# mp3431-boost-tester-mk-2_0_0.net
KiCad netlist of a schematic drawn in EAGLE
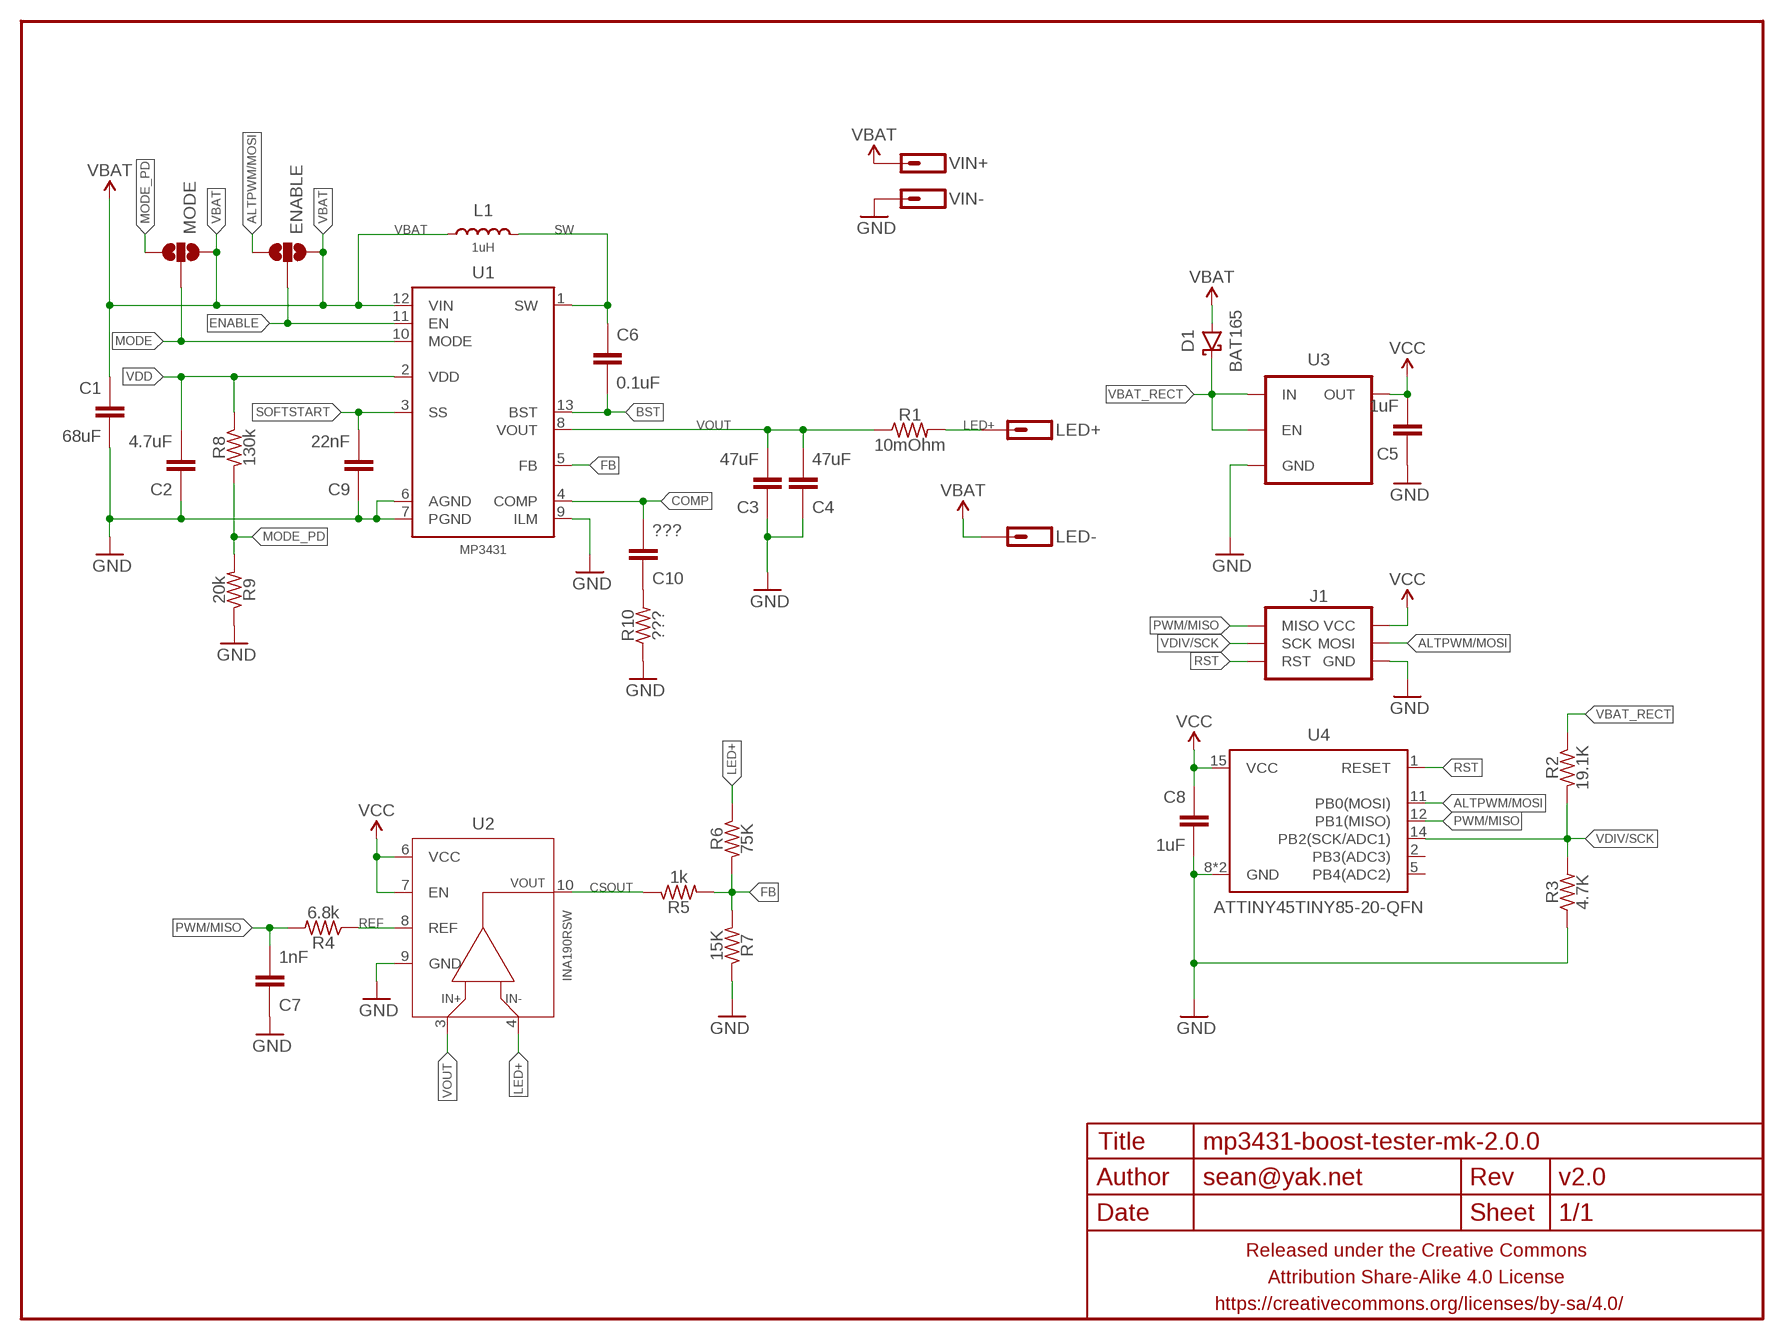
[diagram p0: schematic, sheet 1]

(export (version "E")
  (design (tool "Eeschema 10.0.6"))
  (components
    (comp (ref "C1")
      (value "68uF")
      (footprint "eagle-import:C1206")
      (libsource (lib "eagle-import") (part "CAPACITOR-CERAMICC1206"))
    )
    (comp (ref "C2")
      (value "4.7uF")
      (footprint "eagle-import:C0402")
      (libsource (lib "eagle-import") (part "CAPACITOR-CERAMICC0402"))
    )
    (comp (ref "C3")
      (value "47uF")
      (footprint "eagle-import:C1206")
      (libsource (lib "eagle-import") (part "CAPACITOR-CERAMICC1206"))
    )
    (comp (ref "C4")
      (value "47uF")
      (footprint "eagle-import:C1206")
      (libsource (lib "eagle-import") (part "CAPACITOR-CERAMICC1206"))
    )
    (comp (ref "C5")
      (value "1uF")
      (footprint "eagle-import:C0402")
      (libsource (lib "eagle-import") (part "CAPACITOR-CERAMICC0402"))
    )
    (comp (ref "C6")
      (value "0.1uF")
      (footprint "eagle-import:C0402")
      (libsource (lib "eagle-import") (part "CAPACITOR-CERAMICC0402"))
    )
    (comp (ref "C7")
      (value "1nF")
      (footprint "eagle-import:C0402")
      (libsource (lib "eagle-import") (part "CAPACITOR-CERAMICC0402"))
    )
    (comp (ref "C8")
      (value "1uF")
      (footprint "eagle-import:C0402")
      (libsource (lib "eagle-import") (part "CAPACITOR-CERAMICC0402"))
    )
    (comp (ref "C9")
      (value "22nF")
      (footprint "eagle-import:C0402")
      (libsource (lib "eagle-import") (part "CAPACITOR-CERAMICC0402"))
    )
    (comp (ref "C10")
      (value "???")
      (footprint "eagle-import:C0402")
      (libsource (lib "eagle-import") (part "CAPACITOR-CERAMICC0402"))
    )
    (comp (ref "D1")
      (value "BAT165")
      (footprint "eagle-import:SOD323-SCHOTTKY")
      (libsource (lib "eagle-import") (part "DIODE-SCHOTTKYSOD323"))
    )
    (comp (ref "ENABLE")
      (value "JUMPER-PAD-3-NOSMALL_BOX_SILK")
      (footprint "eagle-import:PAD-JUMPER-3-NO_YES_SILK_SMALL_BOX")
      (libsource (lib "eagle-import") (part "JUMPER-PAD-3-NOSMALL_BOX_SILK"))
    )
    (comp (ref "FRAME1")
      (value "FRAME-LETTERNO_PACKAGE")
      (footprint "eagle-import:DUMMY")
      (fields
        (field (name "DESIGNER") "sean@yak.net")
        (field (name "VERSION") "v2.0")
        (field (name "DESIGNER_1") "sean@yak.net")
        (field (name "VERSION_1") "v2.0")
      )
      (libsource (lib "eagle-import") (part "FRAME-LETTERNO_PACKAGE"))
    )
    (comp (ref "J1")
      (value "AVR_SPI_PRG_6SMD-1.27MM")
      (footprint "eagle-import:2X3-1.27MM-SMD")
      (libsource (lib "eagle-import") (part "AVR_SPI_PRG_6SMD-1.27MM"))
    )
    (comp (ref "L1")
      (value "1uH")
      (footprint "eagle-import:XAL7070")
      (libsource (lib "eagle-import") (part "INDUCTORXAL7070"))
    )
    (comp (ref "LED+")
      (value "M01PTH-1.2MM-NS")
      (footprint "eagle-import:1X01-1.2MM-NS")
      (libsource (lib "eagle-import") (part "M01PTH-1.2MM-NS"))
    )
    (comp (ref "LED-")
      (value "M01PTH-1.2MM-NS")
      (footprint "eagle-import:1X01-1.2MM-NS")
      (libsource (lib "eagle-import") (part "M01PTH-1.2MM-NS"))
    )
    (comp (ref "MODE")
      (value "JUMPER-PAD-3-NOSMALL_BOX_SILK")
      (footprint "eagle-import:PAD-JUMPER-3-NO_YES_SILK_SMALL_BOX")
      (libsource (lib "eagle-import") (part "JUMPER-PAD-3-NOSMALL_BOX_SILK"))
    )
    (comp (ref "R1")
      (value "10mOhm")
      (footprint "eagle-import:R1206")
      (libsource (lib "eagle-import") (part "RESISTORR1206"))
    )
    (comp (ref "R2")
      (value "19.1K")
      (footprint "eagle-import:R0402")
      (libsource (lib "eagle-import") (part "RESISTORR0402"))
    )
    (comp (ref "R3")
      (value "4.7K")
      (footprint "eagle-import:R0402")
      (libsource (lib "eagle-import") (part "RESISTORR0402"))
    )
    (comp (ref "R4")
      (value "6.8k")
      (footprint "eagle-import:R0402")
      (libsource (lib "eagle-import") (part "RESISTORR0402"))
    )
    (comp (ref "R5")
      (value "1k")
      (footprint "eagle-import:R0402")
      (libsource (lib "eagle-import") (part "RESISTORR0402"))
    )
    (comp (ref "R6")
      (value "75K")
      (footprint "eagle-import:R0402")
      (libsource (lib "eagle-import") (part "RESISTORR0402"))
    )
    (comp (ref "R7")
      (value "15K")
      (footprint "eagle-import:R0402")
      (libsource (lib "eagle-import") (part "RESISTORR0402"))
    )
    (comp (ref "R8")
      (value "130k")
      (footprint "eagle-import:R0402")
      (libsource (lib "eagle-import") (part "RESISTORR0402"))
    )
    (comp (ref "R9")
      (value "20k")
      (footprint "eagle-import:R0402")
      (libsource (lib "eagle-import") (part "RESISTORR0402"))
    )
    (comp (ref "R10")
      (value "???")
      (footprint "eagle-import:R0402")
      (libsource (lib "eagle-import") (part "RESISTORR0402"))
    )
    (comp (ref "U1")
      (value "MP3431")
      (footprint "eagle-import:MP3431")
      (libsource (lib "eagle-import") (part "MP3431"))
    )
    (comp (ref "U2")
      (value "INA190RSW")
      (footprint "eagle-import:UQFN-10")
      (libsource (lib "eagle-import") (part "INA190RSW"))
    )
    (comp (ref "U3")
      (value "V_REG_ENTLV700")
      (footprint "eagle-import:SC70")
      (libsource (lib "eagle-import") (part "V_REG_ENTLV700"))
    )
    (comp (ref "U4")
      (value "ATTINY45TINY85-20-QFN")
      (footprint "eagle-import:QFN20")
      (libsource (lib "eagle-import") (part "ATTINY45TINY85-20-QFN"))
    )
    (comp (ref "VIN+")
      (value "M01PTH-1.2MM-NS")
      (footprint "eagle-import:1X01-1.2MM-NS")
      (libsource (lib "eagle-import") (part "M01PTH-1.2MM-NS"))
    )
    (comp (ref "VIN-")
      (value "M01PTH-1.2MM-NS")
      (footprint "eagle-import:1X01-1.2MM-NS")
      (libsource (lib "eagle-import") (part "M01PTH-1.2MM-NS"))
    )
  )
  (nets
    (net (code "1") (name "/CSOUT") (class "Default")
      (node (ref "R5") (pin "1") (pinfunction "1_1") (pintype "passive"))
      (node (ref "U2") (pin "10") (pinfunction "OUT_10") (pintype "bidirectional"))
    )
    (net (code "2") (name "/REF") (class "Default")
      (node (ref "R4") (pin "1") (pinfunction "1_1") (pintype "passive"))
      (node (ref "U2") (pin "8") (pinfunction "REF_8") (pintype "bidirectional"))
    )
    (net (code "3") (name "/SW") (class "Default")
      (node (ref "C6") (pin "1") (pinfunction "1_1") (pintype "passive"))
      (node (ref "L1") (pin "P$2") (pinfunction "2_P$2") (pintype "passive"))
      (node (ref "U1") (pin "1") (pinfunction "SW_1") (pintype "bidirectional"))
    )
    (net (code "4") (name "ALTPWM{slash}MOSI") (class "Default")
      (node (ref "ENABLE") (pin "3") (pinfunction "3_3") (pintype "passive"))
      (node (ref "J1") (pin "4") (pinfunction "MOSI_4") (pintype "passive"))
      (node (ref "U4") (pin "11") (pinfunction "PB0(MOSI)_11") (pintype "bidirectional"))
    )
    (net (code "5") (name "BST") (class "Default")
      (node (ref "C6") (pin "2") (pinfunction "2_2") (pintype "passive"))
      (node (ref "U1") (pin "13") (pinfunction "BST_13") (pintype "bidirectional"))
    )
    (net (code "6") (name "COMP") (class "Default")
      (node (ref "C10") (pin "2") (pinfunction "2_2") (pintype "passive"))
      (node (ref "U1") (pin "4") (pinfunction "COMP_4") (pintype "bidirectional"))
    )
    (net (code "7") (name "ENABLE") (class "Default")
      (node (ref "ENABLE") (pin "2") (pinfunction "2_2") (pintype "passive"))
      (node (ref "U1") (pin "11") (pinfunction "EN_11") (pintype "bidirectional"))
    )
    (net (code "8") (name "FB") (class "Default")
      (node (ref "R5") (pin "2") (pinfunction "2_2") (pintype "passive"))
      (node (ref "R6") (pin "2") (pinfunction "2_2") (pintype "passive"))
      (node (ref "R7") (pin "2") (pinfunction "2_2") (pintype "passive"))
      (node (ref "U1") (pin "5") (pinfunction "FB_5") (pintype "bidirectional"))
    )
    (net (code "9") (name "GND") (class "Default")
      (node (ref "C1") (pin "2") (pinfunction "2_2") (pintype "passive"))
      (node (ref "C2") (pin "1") (pinfunction "1_1") (pintype "passive"))
      (node (ref "C3") (pin "1") (pinfunction "1_1") (pintype "passive"))
      (node (ref "C4") (pin "1") (pinfunction "1_1") (pintype "passive"))
      (node (ref "C5") (pin "1") (pinfunction "1_1") (pintype "passive"))
      (node (ref "C7") (pin "1") (pinfunction "1_1") (pintype "passive"))
      (node (ref "C8") (pin "2") (pinfunction "2_2") (pintype "passive"))
      (node (ref "C9") (pin "1") (pinfunction "1_1") (pintype "passive"))
      (node (ref "J1") (pin "6") (pinfunction "GND_6") (pintype "passive"))
      (node (ref "R10") (pin "1") (pinfunction "1_1") (pintype "passive"))
      (node (ref "R3") (pin "1") (pinfunction "1_1") (pintype "passive"))
      (node (ref "R7") (pin "1") (pinfunction "1_1") (pintype "passive"))
      (node (ref "R9") (pin "1") (pinfunction "1_1") (pintype "passive"))
      (node (ref "U1") (pin "6") (pinfunction "AGND_6") (pintype "bidirectional"))
      (node (ref "U1") (pin "7") (pinfunction "PGND_7") (pintype "bidirectional"))
      (node (ref "U1") (pin "9") (pinfunction "ILM_9") (pintype "bidirectional"))
      (node (ref "U2") (pin "9") (pinfunction "GND_9") (pintype "bidirectional"))
      (node (ref "U3") (pin "2") (pinfunction "GND_2") (pintype "input"))
      (node (ref "U4") (pin "8") (pinfunction "GND_8") (pintype "bidirectional"))
      (node (ref "U4") (pin "PAD") (pinfunction "GND_PAD") (pintype "bidirectional"))
      (node (ref "VIN-") (pin "P$1") (pinfunction "1_P$1") (pintype "passive"))
    )
    (net (code "10") (name "LED+") (class "Default")
      (node (ref "LED+") (pin "P$1") (pinfunction "1_P$1") (pintype "passive"))
      (node (ref "R1") (pin "2") (pinfunction "2_2") (pintype "passive"))
      (node (ref "R6") (pin "1") (pinfunction "1_1") (pintype "passive"))
      (node (ref "U2") (pin "4") (pinfunction "VIN-_4") (pintype "bidirectional"))
    )
    (net (code "11") (name "MODE") (class "Default")
      (node (ref "MODE") (pin "2") (pinfunction "2_2") (pintype "passive"))
      (node (ref "U1") (pin "10") (pinfunction "MODE_10") (pintype "bidirectional"))
    )
    (net (code "12") (name "MODE_PD") (class "Default")
      (node (ref "MODE") (pin "3") (pinfunction "3_3") (pintype "passive"))
      (node (ref "R8") (pin "2") (pinfunction "2_2") (pintype "passive"))
      (node (ref "R9") (pin "2") (pinfunction "2_2") (pintype "passive"))
    )
    (net (code "13") (name "Net-(C10-Pad1)") (class "Default")
      (node (ref "C10") (pin "1") (pinfunction "1_1") (pintype "passive"))
      (node (ref "R10") (pin "2") (pinfunction "2_2") (pintype "passive"))
    )
    (net (code "14") (name "PWM{slash}MISO") (class "Default")
      (node (ref "C7") (pin "2") (pinfunction "2_2") (pintype "passive"))
      (node (ref "J1") (pin "1") (pinfunction "MISO_1") (pintype "passive"))
      (node (ref "R4") (pin "2") (pinfunction "2_2") (pintype "passive"))
      (node (ref "U4") (pin "12") (pinfunction "PB1(MISO)_12") (pintype "bidirectional"))
    )
    (net (code "15") (name "RST") (class "Default")
      (node (ref "J1") (pin "5") (pinfunction "RST_5") (pintype "passive"))
      (node (ref "U4") (pin "1") (pinfunction "RESET_1") (pintype "bidirectional"))
    )
    (net (code "16") (name "SOFTSTART") (class "Default")
      (node (ref "C9") (pin "2") (pinfunction "2_2") (pintype "passive"))
      (node (ref "U1") (pin "3") (pinfunction "SS_3") (pintype "bidirectional"))
    )
    (net (code "17") (name "VBAT") (class "Default")
      (node (ref "C1") (pin "1") (pinfunction "1_1") (pintype "passive"))
      (node (ref "D1") (pin "A") (pinfunction "A_A") (pintype "passive"))
      (node (ref "ENABLE") (pin "1") (pinfunction "1_1") (pintype "passive"))
      (node (ref "L1") (pin "P$1") (pinfunction "1_P$1") (pintype "passive"))
      (node (ref "LED-") (pin "P$1") (pinfunction "1_P$1") (pintype "passive"))
      (node (ref "MODE") (pin "1") (pinfunction "1_1") (pintype "passive"))
      (node (ref "U1") (pin "12") (pinfunction "VIN_12") (pintype "bidirectional"))
      (node (ref "VIN+") (pin "P$1") (pinfunction "1_P$1") (pintype "passive"))
    )
    (net (code "18") (name "VBAT_RECT") (class "Default")
      (node (ref "D1") (pin "C") (pinfunction "C_C") (pintype "passive"))
      (node (ref "R2") (pin "1") (pinfunction "1_1") (pintype "passive"))
      (node (ref "U3") (pin "1") (pinfunction "IN_1") (pintype "input"))
      (node (ref "U3") (pin "3") (pinfunction "EN_3") (pintype "input"))
    )
    (net (code "19") (name "VCC") (class "Default")
      (node (ref "C5") (pin "2") (pinfunction "2_2") (pintype "passive"))
      (node (ref "C8") (pin "1") (pinfunction "1_1") (pintype "passive"))
      (node (ref "J1") (pin "2") (pinfunction "VCC_2") (pintype "passive"))
      (node (ref "U2") (pin "6") (pinfunction "VCC_6") (pintype "bidirectional"))
      (node (ref "U2") (pin "7") (pinfunction "EN_7") (pintype "bidirectional"))
      (node (ref "U3") (pin "5") (pinfunction "OUT_5") (pintype "passive"))
      (node (ref "U4") (pin "15") (pinfunction "VCC_15") (pintype "bidirectional"))
    )
    (net (code "20") (name "VDD") (class "Default")
      (node (ref "C2") (pin "2") (pinfunction "2_2") (pintype "passive"))
      (node (ref "R8") (pin "1") (pinfunction "1_1") (pintype "passive"))
      (node (ref "U1") (pin "2") (pinfunction "VDD_2") (pintype "bidirectional"))
    )
    (net (code "21") (name "VDIV{slash}SCK") (class "Default")
      (node (ref "J1") (pin "3") (pinfunction "SCK_3") (pintype "passive"))
      (node (ref "R2") (pin "2") (pinfunction "2_2") (pintype "passive"))
      (node (ref "R3") (pin "2") (pinfunction "2_2") (pintype "passive"))
      (node (ref "U4") (pin "14") (pinfunction "PB2(SCK/ADC1)_14") (pintype "bidirectional"))
    )
    (net (code "22") (name "VOUT") (class "Default")
      (node (ref "C3") (pin "2") (pinfunction "2_2") (pintype "passive"))
      (node (ref "C4") (pin "2") (pinfunction "2_2") (pintype "passive"))
      (node (ref "R1") (pin "1") (pinfunction "1_1") (pintype "passive"))
      (node (ref "U1") (pin "8") (pinfunction "VOUT_8") (pintype "bidirectional"))
      (node (ref "U2") (pin "3") (pinfunction "VIN+_3") (pintype "bidirectional"))
    )
    (net (code "23") (name "unconnected-(U4-PB3(ADC3)-Pad2)") (class "Default")
      (node (ref "U4") (pin "2") (pinfunction "PB3(ADC3)_2") (pintype "bidirectional"))
    )
    (net (code "24") (name "unconnected-(U4-PB4(ADC2)-Pad5)") (class "Default")
      (node (ref "U4") (pin "5") (pinfunction "PB4(ADC2)_5") (pintype "bidirectional"))
    )
  )
)
